# schematic.net
KiCad netlist of a schematic drawn in Altium Designer
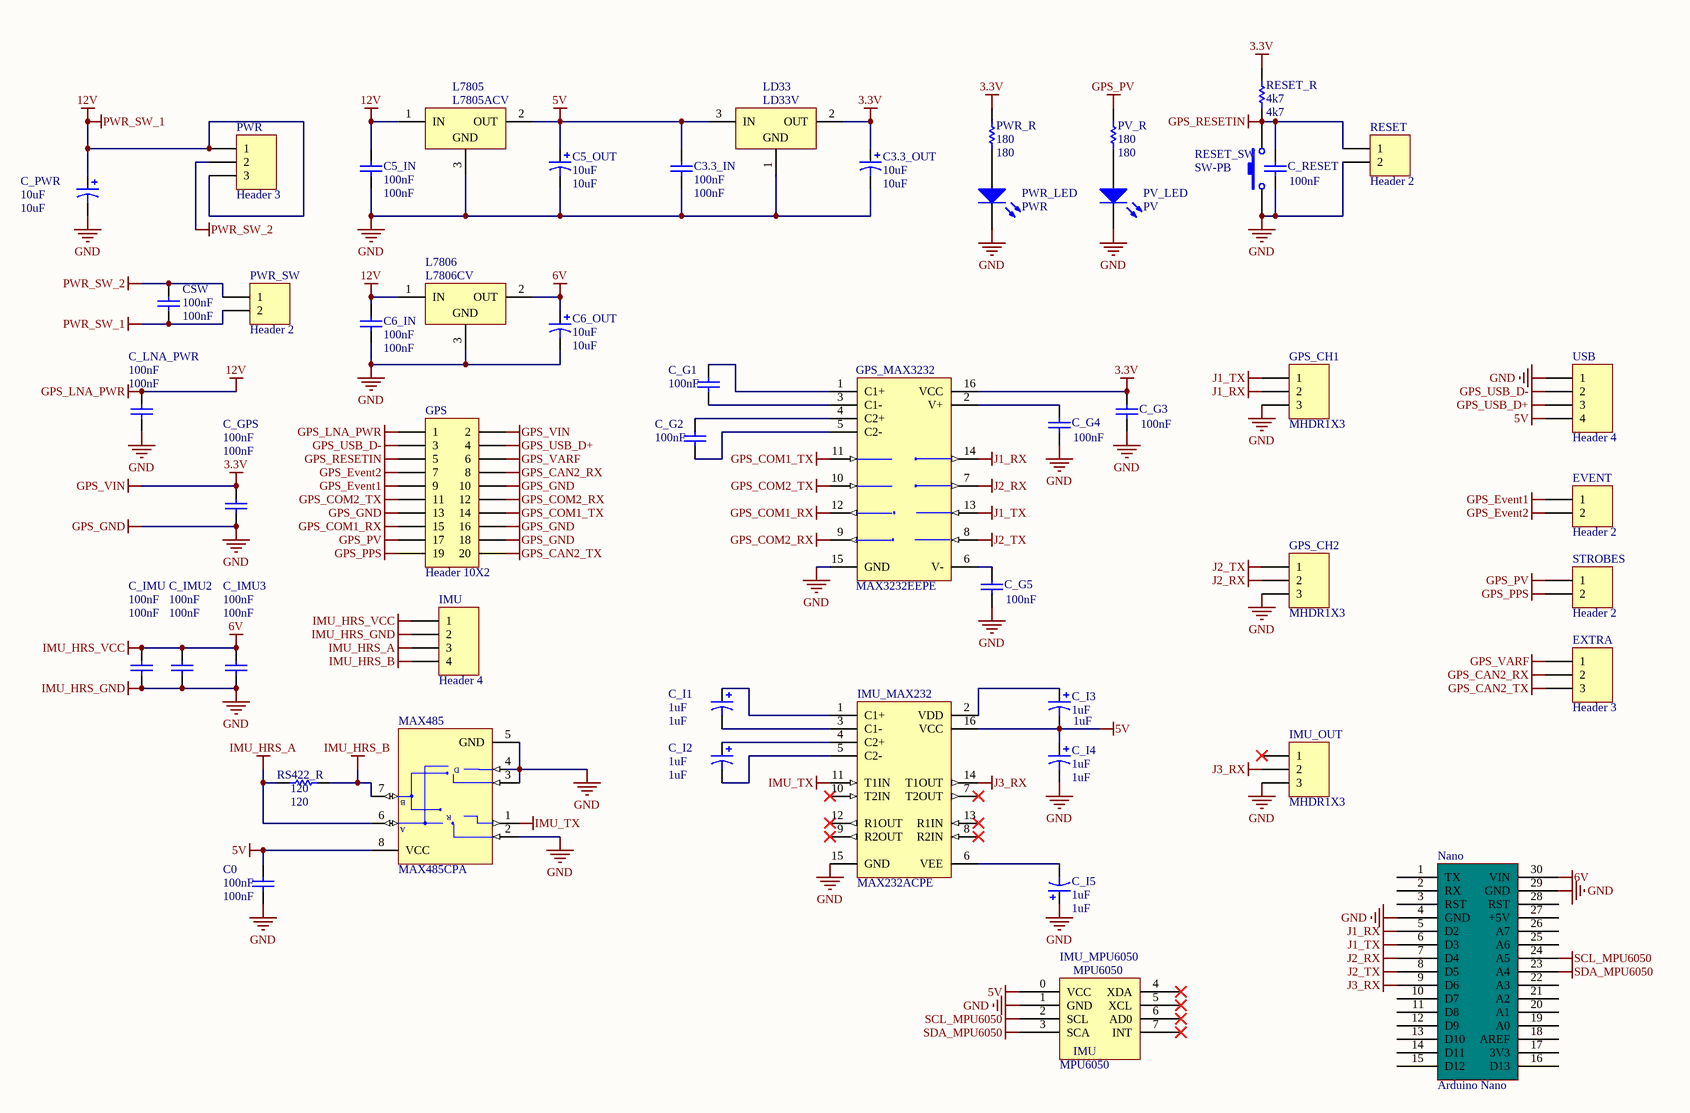
[diagram p0: schematic.SchDoc]

(export (version "E")
  (design (tool "Eeschema 10.0.6"))
  (components
    (comp (ref "C0")
      (value "100nF")
      (footprint "C_NANO_HOLES")
      (description "Capacitor")
      (fields (field (name "ALTIUM_VALUE") "100nF") (field (name "PUBLISHER") "Altium Limited"))
      (libsource (lib "Miscellaneous Devices") (part "Cap"))
    )
    (comp (ref "C3.3_IN")
      (value "100nF")
      (footprint "C_NANO_HOLES")
      (description "Capacitor")
      (fields (field (name "ALTIUM_VALUE") "100nF") (field (name "PUBLISHER") "Altium Limited"))
      (libsource (lib "Miscellaneous Devices") (part "Cap"))
    )
    (comp (ref "C3.3_OUT")
      (value "10uF")
      (footprint "B")
      (description "Polarized Capacitor (Radial)")
      (fields (field (name "ALTIUM_VALUE") "10uF") (field (name "PUBLISHER") "Altium Limited"))
      (libsource (lib "Miscellaneous Devices") (part "Cap Pol1"))
    )
    (comp (ref "C5_IN")
      (value "100nF")
      (footprint "C_NANO_HOLES")
      (description "Capacitor")
      (fields (field (name "ALTIUM_VALUE") "100nF") (field (name "PUBLISHER") "Altium Limited"))
      (libsource (lib "Miscellaneous Devices") (part "Cap"))
    )
    (comp (ref "C5_OUT")
      (value "10uF")
      (footprint "B")
      (description "Polarized Capacitor (Radial)")
      (fields (field (name "ALTIUM_VALUE") "10uF") (field (name "PUBLISHER") "Altium Limited"))
      (libsource (lib "Miscellaneous Devices") (part "Cap Pol1"))
    )
    (comp (ref "C6_IN")
      (value "100nF")
      (footprint "C_NANO_HOLES")
      (description "Capacitor")
      (fields (field (name "ALTIUM_VALUE") "100nF") (field (name "PUBLISHER") "Altium Limited"))
      (libsource (lib "Miscellaneous Devices") (part "Cap"))
    )
    (comp (ref "C6_OUT")
      (value "10uF")
      (footprint "B")
      (description "Polarized Capacitor (Radial)")
      (fields (field (name "ALTIUM_VALUE") "10uF") (field (name "PUBLISHER") "Altium Limited"))
      (libsource (lib "Miscellaneous Devices") (part "Cap Pol1"))
    )
    (comp (ref "CSW")
      (value "100nF")
      (footprint "C_NANO_HOLES")
      (description "Capacitor")
      (fields (field (name "ALTIUM_VALUE") "100nF") (field (name "PUBLISHER") "Altium Limited"))
      (libsource (lib "Miscellaneous Devices") (part "Cap"))
    )
    (comp (ref "C_G1")
      (value "100nF")
      (footprint "C_NANO_HOLES")
      (description "Capacitor")
      (fields (field (name "PUBLISHER") "Altium Limited"))
      (libsource (lib "Miscellaneous Devices") (part "Cap"))
    )
    (comp (ref "C_G2")
      (value "100nF")
      (footprint "C_NANO_HOLES")
      (description "Capacitor")
      (fields (field (name "PUBLISHER") "Altium Limited"))
      (libsource (lib "Miscellaneous Devices") (part "Cap"))
    )
    (comp (ref "C_G3")
      (value "100nF")
      (footprint "C_NANO_HOLES")
      (description "Capacitor")
      (fields (field (name "PUBLISHER") "Altium Limited"))
      (libsource (lib "Miscellaneous Devices") (part "Cap"))
    )
    (comp (ref "C_G4")
      (value "100nF")
      (footprint "C_NANO_HOLES")
      (description "Capacitor")
      (fields (field (name "PUBLISHER") "Altium Limited"))
      (libsource (lib "Miscellaneous Devices") (part "Cap"))
    )
    (comp (ref "C_G5")
      (value "100nF")
      (footprint "C_NANO_HOLES")
      (description "Capacitor")
      (fields (field (name "PUBLISHER") "Altium Limited"))
      (libsource (lib "Miscellaneous Devices") (part "Cap"))
    )
    (comp (ref "C_GPS")
      (value "100nF")
      (footprint "C_NANO_HOLES")
      (description "Capacitor")
      (fields (field (name "ALTIUM_VALUE") "100nF") (field (name "PUBLISHER") "Altium Limited"))
      (libsource (lib "Miscellaneous Devices") (part "Cap"))
    )
    (comp (ref "C_I1")
      (value "1uF")
      (footprint "B")
      (description "Polarized Capacitor (Radial)")
      (fields (field (name "ALTIUM_VALUE") "1uF") (field (name "PUBLISHER") "Altium Limited"))
      (libsource (lib "Miscellaneous Devices") (part "Cap Pol1"))
    )
    (comp (ref "C_I2")
      (value "1uF")
      (footprint "B")
      (description "Polarized Capacitor (Radial)")
      (fields (field (name "ALTIUM_VALUE") "1uF") (field (name "PUBLISHER") "Altium Limited"))
      (libsource (lib "Miscellaneous Devices") (part "Cap Pol1"))
    )
    (comp (ref "C_I3")
      (value "1uF")
      (footprint "B")
      (description "Polarized Capacitor (Radial)")
      (fields (field (name "ALTIUM_VALUE") "1uF") (field (name "PUBLISHER") "Altium Limited"))
      (libsource (lib "Miscellaneous Devices") (part "Cap Pol1"))
    )
    (comp (ref "C_I4")
      (value "1uF")
      (footprint "B")
      (description "Polarized Capacitor (Radial)")
      (fields (field (name "ALTIUM_VALUE") "1uF") (field (name "PUBLISHER") "Altium Limited"))
      (libsource (lib "Miscellaneous Devices") (part "Cap Pol1"))
    )
    (comp (ref "C_I5")
      (value "1uF")
      (footprint "B")
      (description "Polarized Capacitor (Radial)")
      (fields (field (name "ALTIUM_VALUE") "1uF") (field (name "PUBLISHER") "Altium Limited"))
      (libsource (lib "Miscellaneous Devices") (part "Cap Pol1"))
    )
    (comp (ref "C_IMU")
      (value "100nF")
      (footprint "C_NANO_HOLES")
      (description "Capacitor")
      (fields (field (name "ALTIUM_VALUE") "100nF") (field (name "PUBLISHER") "Altium Limited"))
      (libsource (lib "Miscellaneous Devices") (part "Cap"))
    )
    (comp (ref "C_IMU2")
      (value "100nF")
      (footprint "C_NANO_HOLES")
      (description "Capacitor")
      (fields (field (name "ALTIUM_VALUE") "100nF") (field (name "PUBLISHER") "Altium Limited"))
      (libsource (lib "Miscellaneous Devices") (part "Cap"))
    )
    (comp (ref "C_IMU3")
      (value "100nF")
      (footprint "C_NANO_HOLES")
      (description "Capacitor")
      (fields (field (name "ALTIUM_VALUE") "100nF") (field (name "PUBLISHER") "Altium Limited"))
      (libsource (lib "Miscellaneous Devices") (part "Cap"))
    )
    (comp (ref "C_LNA_PWR")
      (value "100nF")
      (footprint "C_NANO_HOLES")
      (description "Capacitor")
      (fields (field (name "ALTIUM_VALUE") "100nF") (field (name "PUBLISHER") "Altium Limited"))
      (libsource (lib "Miscellaneous Devices") (part "Cap"))
    )
    (comp (ref "C_PWR")
      (value "10uF")
      (footprint "B")
      (description "Polarized Capacitor (Radial)")
      (fields (field (name "ALTIUM_VALUE") "10uF") (field (name "PUBLISHER") "Altium Limited"))
      (libsource (lib "Miscellaneous Devices") (part "Cap Pol1"))
    )
    (comp (ref "C_RESET")
      (value "100nF")
      (footprint "C_NANO_HOLES")
      (description "Capacitor")
      (fields (field (name "PUBLISHER") "Altium Limited"))
      (libsource (lib "Miscellaneous Devices") (part "Cap"))
    )
    (comp (ref "EVENT")
      (value "Header 2")
      (footprint "HDR1X2")
      (description "Header, 2-Pin")
      (fields (field (name "PUBLISHER") "Altium Limited"))
      (libsource (lib "Miscellaneous Connectors") (part "Header 2"))
    )
    (comp (ref "EXTRA")
      (value "Header 3")
      (footprint "HDR1X3")
      (description "Header, 3-Pin")
      (fields (field (name "PUBLISHER") "Altium Limited"))
      (libsource (lib "Miscellaneous Connectors") (part "Header 3"))
    )
    (comp (ref "GPS")
      (value "Header 10X2")
      (footprint "HDR2x10_2mm")
      (description "Header, 10-Pin, Dual row")
      (fields (field (name "PUBLISHER") "Altium Limited"))
      (libsource (lib "Miscellaneous Connectors") (part "Header 10X2"))
    )
    (comp (ref "GPS_CH1")
      (value "MHDR1X3")
      (footprint "HDR1X3")
      (description "Header, 3-Pin")
      (fields (field (name "PUBLISHER") "Altium Limited"))
      (libsource (lib "Miscellaneous Connectors") (part "MHDR1X3"))
    )
    (comp (ref "GPS_CH2")
      (value "MHDR1X3")
      (footprint "HDR1X3")
      (description "Header, 3-Pin")
      (fields (field (name "PUBLISHER") "Altium Limited"))
      (libsource (lib "Miscellaneous Connectors") (part "MHDR1X3"))
    )
    (comp (ref "GPS_MAX3232")
      (value "MAX3232EEPE")
      (footprint "Maxim Footprints:PE16")
      (description "±15kV ESD-Protected, 3.0V to 5.5V, Low-Power, up to 250kbps, True RS-232 Transceiver")
      (fields (field (name "PUBLISHER") "Altium Limited"))
      (libsource (lib "Maxim Communication Transceiver") (part "MAX3232EEPE"))
    )
    (comp (ref "IMU")
      (value "Header 4")
      (footprint "HDR1X4")
      (description "Header, 4-Pin")
      (fields (field (name "PUBLISHER") "Altium Limited"))
      (libsource (lib "Miscellaneous Connectors") (part "Header 4"))
    )
    (comp (ref "IMU_MAX232")
      (value "MAX232ACPE")
      (footprint "PE16A")
      (description "+5V Powered, Multi-Channel RS-232 Driver/Receiver")
      (fields (field (name "PUBLISHER") "Altium Limited"))
      (libsource (lib "Maxim Communication Transceiver") (part "MAX232ACPE"))
    )
    (comp (ref "IMU_MPU6050")
      (value "MPU6050")
      (footprint "MPU6050")
      (libsource (lib "IMU_MPU6050") (part "Component_1"))
    )
    (comp (ref "IMU_OUT")
      (value "MHDR1X3")
      (footprint "HDR1X3")
      (description "Header, 3-Pin")
      (fields (field (name "PUBLISHER") "Altium Limited"))
      (libsource (lib "Miscellaneous Connectors") (part "MHDR1X3"))
    )
    (comp (ref "L7805")
      (value "L7805ACV")
      (footprint "TO220ABN")
      (description "Precision 1A Regulator")
      (fields (field (name "PUBLISHER") "Altium Limited"))
      (libsource (lib "ST Power Mgt Voltage Regulator") (part "L7805ACV"))
    )
    (comp (ref "L7806")
      (value "L7806CV")
      (footprint "TO220ABN")
      (description "Positive Voltage Regulator")
      (fields (field (name "PUBLISHER") "Altium Limited"))
      (libsource (lib "ST Power Mgt Voltage Regulator") (part "L7806CV"))
    )
    (comp (ref "LD33")
      (value "LD33V")
      (footprint "T03B")
      (description "800mA Low-Dropout Linear Regulator")
      (fields
        (field (name "PARTNUMBER") "LM1117T-3.3")
        (field (name "MANUFACTURER") "National Semiconductor")
        (field (name "PUBLISHER") "Altium Limited")
      )
      (libsource (lib "NSC LDO") (part "LM1117T-3.3"))
    )
    (comp (ref "MAX485")
      (value "MAX485CPA")
      (footprint "PA8")
      (description "Low-Power, Slew-Rate-Limited RS-485/RS-422 Transceiver")
      (fields (field (name "PUBLISHER") "Altium Limited"))
      (libsource (lib "Maxim Communication Transceiver") (part "MAX485CPA"))
    )
    (comp (ref "Nano")
      (value "Arduino Nano")
      (footprint "Nano:ArduinoNano")
      (libsource (lib "Nano") (part "Component_1"))
    )
    (comp (ref "PV_LED")
      (value "PV")
      (footprint "HDR1X2")
      (description "Typical INFRARED GaAs LED")
      (fields (field (name "PUBLISHER") "Altium Limited"))
      (libsource (lib "Miscellaneous Devices") (part "LED0"))
    )
    (comp (ref "PV_R")
      (value "180")
      (footprint "AXIAL-0.3")
      (description "Resistor")
      (fields (field (name "ALTIUM_VALUE") "180") (field (name "PUBLISHER") "Altium Limited"))
      (libsource (lib "Miscellaneous Devices") (part "Res1"))
    )
    (comp (ref "PWR")
      (value "Header 3")
      (footprint "Miscellaneous Connectors:HDR1X3")
      (description "Header, 3-Pin, Right Angle")
      (fields (field (name "PUBLISHER") "Altium Limited"))
      (libsource (lib "Miscellaneous Connectors") (part "Header 3H"))
    )
    (comp (ref "PWR_LED")
      (value "PWR")
      (footprint "HDR1X2")
      (description "Typical INFRARED GaAs LED")
      (fields (field (name "PUBLISHER") "Altium Limited"))
      (libsource (lib "Miscellaneous Devices") (part "LED0"))
    )
    (comp (ref "PWR_R")
      (value "180")
      (footprint "AXIAL-0.3")
      (description "Resistor")
      (fields (field (name "ALTIUM_VALUE") "180") (field (name "PUBLISHER") "Altium Limited"))
      (libsource (lib "Miscellaneous Devices") (part "Res1"))
    )
    (comp (ref "PWR_SW")
      (value "Header 2")
      (footprint "Miscellaneous Connectors:HDR1X2")
      (description "Header, 2-Pin, Right Angle")
      (fields (field (name "PUBLISHER") "Altium Limited"))
      (libsource (lib "Miscellaneous Connectors") (part "Header 2H"))
    )
    (comp (ref "RESET")
      (value "Header 2")
      (footprint "Miscellaneous Connectors:HDR1X2")
      (description "Header, 2-Pin, Right Angle")
      (fields (field (name "PUBLISHER") "Altium Limited"))
      (libsource (lib "Miscellaneous Connectors") (part "Header 2H"))
    )
    (comp (ref "RESET_R")
      (value "4k7")
      (footprint "AXIAL-0.3")
      (description "Resistor")
      (fields (field (name "ALTIUM_VALUE") "4k7") (field (name "PUBLISHER") "Altium Limited"))
      (libsource (lib "Miscellaneous Devices") (part "Res1"))
    )
    (comp (ref "RESET_SW")
      (value "SW-PB")
      (footprint "PUSHBUTTON")
      (description "Switch")
      (fields (field (name "PUBLISHER") "Altium Limited"))
      (libsource (lib "Miscellaneous Devices") (part "SW-PB"))
    )
    (comp (ref "RS422_R")
      (value "120")
      (footprint "AXIAL-0.3")
      (description "Resistor")
      (fields (field (name "ALTIUM_VALUE") "120") (field (name "PUBLISHER") "Altium Limited"))
      (libsource (lib "Miscellaneous Devices") (part "Res1"))
    )
    (comp (ref "STROBES")
      (value "Header 2")
      (footprint "HDR1X2")
      (description "Header, 2-Pin")
      (fields (field (name "PUBLISHER") "Altium Limited"))
      (libsource (lib "Miscellaneous Connectors") (part "Header 2"))
    )
    (comp (ref "USB")
      (value "Header 4")
      (footprint "HDR1X4")
      (description "Header, 4-Pin")
      (fields (field (name "PUBLISHER") "Altium Limited"))
      (libsource (lib "Miscellaneous Connectors") (part "Header 4"))
    )
  )
  (nets
    (net (code "1") (name "3.3V") (class "Default")
      (node (ref "C3.3_OUT") (pin "1") (pinfunction "1_1") (pintype "passive"))
      (node (ref "C_G3") (pin "2") (pinfunction "2_2") (pintype "passive"))
      (node (ref "C_GPS") (pin "2") (pinfunction "2_2") (pintype "passive"))
      (node (ref "GPS") (pin "2") (pinfunction "2_2") (pintype "passive"))
      (node (ref "GPS_MAX3232") (pin "16") (pinfunction "VCC_16") (pintype "power_in"))
      (node (ref "LD33") (pin "2") (pinfunction "OUT_2") (pintype "power_in"))
      (node (ref "PWR_R") (pin "2") (pinfunction "2_2") (pintype "passive"))
      (node (ref "RESET_R") (pin "2") (pinfunction "2_2") (pintype "passive"))
    )
    (net (code "2") (name "5V") (class "Default")
      (node (ref "C0") (pin "2") (pinfunction "2_2") (pintype "passive"))
      (node (ref "C3.3_IN") (pin "1") (pinfunction "1_1") (pintype "passive"))
      (node (ref "C5_OUT") (pin "1") (pinfunction "1_1") (pintype "passive"))
      (node (ref "C_I3") (pin "2") (pinfunction "2_2") (pintype "passive"))
      (node (ref "C_I4") (pin "1") (pinfunction "1_1") (pintype "passive"))
      (node (ref "IMU_MAX232") (pin "16") (pinfunction "VCC_16") (pintype "power_in"))
      (node (ref "IMU_MPU6050") (pin "0") (pinfunction "VCC_0") (pintype "passive"))
      (node (ref "L7805") (pin "2") (pinfunction "OUT_2") (pintype "power_in"))
      (node (ref "LD33") (pin "3") (pinfunction "IN_3") (pintype "power_in"))
      (node (ref "MAX485") (pin "8") (pinfunction "VCC_8") (pintype "power_in"))
      (node (ref "USB") (pin "4") (pinfunction "4_4") (pintype "passive"))
    )
    (net (code "3") (name "6V") (class "Default")
      (node (ref "C6_OUT") (pin "1") (pinfunction "1_1") (pintype "passive"))
      (node (ref "C_IMU") (pin "2") (pinfunction "2_2") (pintype "passive"))
      (node (ref "C_IMU2") (pin "2") (pinfunction "2_2") (pintype "passive"))
      (node (ref "C_IMU3") (pin "2") (pinfunction "2_2") (pintype "passive"))
      (node (ref "IMU") (pin "1") (pinfunction "1_1") (pintype "passive"))
      (node (ref "L7806") (pin "2") (pinfunction "OUT_2") (pintype "power_in"))
      (node (ref "Nano") (pin "30") (pinfunction "VIN_30") (pintype "passive"))
    )
    (net (code "4") (name "12V") (class "Default")
      (node (ref "C5_IN") (pin "1") (pinfunction "1_1") (pintype "passive"))
      (node (ref "C6_IN") (pin "1") (pinfunction "1_1") (pintype "passive"))
      (node (ref "CSW") (pin "2") (pinfunction "2_2") (pintype "passive"))
      (node (ref "C_LNA_PWR") (pin "2") (pinfunction "2_2") (pintype "passive"))
      (node (ref "C_PWR") (pin "1") (pinfunction "1_1") (pintype "passive"))
      (node (ref "GPS") (pin "1") (pinfunction "1_1") (pintype "passive"))
      (node (ref "L7805") (pin "1") (pinfunction "IN_1") (pintype "power_in"))
      (node (ref "L7806") (pin "1") (pinfunction "IN_1") (pintype "power_in"))
      (node (ref "PWR") (pin "1") (pinfunction "1_1") (pintype "passive"))
      (node (ref "PWR") (pin "3") (pinfunction "3_3") (pintype "passive"))
      (node (ref "PWR_SW") (pin "2") (pinfunction "2_2") (pintype "passive"))
    )
    (net (code "5") (name "GND") (class "Default")
      (node (ref "C0") (pin "1") (pinfunction "1_1") (pintype "passive"))
      (node (ref "C3.3_IN") (pin "2") (pinfunction "2_2") (pintype "passive"))
      (node (ref "C3.3_OUT") (pin "2") (pinfunction "2_2") (pintype "passive"))
      (node (ref "C5_IN") (pin "2") (pinfunction "2_2") (pintype "passive"))
      (node (ref "C5_OUT") (pin "2") (pinfunction "2_2") (pintype "passive"))
      (node (ref "C6_IN") (pin "2") (pinfunction "2_2") (pintype "passive"))
      (node (ref "C6_OUT") (pin "2") (pinfunction "2_2") (pintype "passive"))
      (node (ref "C_G3") (pin "1") (pinfunction "1_1") (pintype "passive"))
      (node (ref "C_G4") (pin "1") (pinfunction "1_1") (pintype "passive"))
      (node (ref "C_G5") (pin "1") (pinfunction "1_1") (pintype "passive"))
      (node (ref "C_GPS") (pin "1") (pinfunction "1_1") (pintype "passive"))
      (node (ref "C_I4") (pin "2") (pinfunction "2_2") (pintype "passive"))
      (node (ref "C_I5") (pin "1") (pinfunction "1_1") (pintype "passive"))
      (node (ref "C_IMU") (pin "1") (pinfunction "1_1") (pintype "passive"))
      (node (ref "C_IMU2") (pin "1") (pinfunction "1_1") (pintype "passive"))
      (node (ref "C_IMU3") (pin "1") (pinfunction "1_1") (pintype "passive"))
      (node (ref "C_LNA_PWR") (pin "1") (pinfunction "1_1") (pintype "passive"))
      (node (ref "C_PWR") (pin "2") (pinfunction "2_2") (pintype "passive"))
      (node (ref "C_RESET") (pin "1") (pinfunction "1_1") (pintype "passive"))
      (node (ref "GPS") (pin "10") (pinfunction "10_10") (pintype "passive"))
      (node (ref "GPS") (pin "13") (pinfunction "13_13") (pintype "passive"))
      (node (ref "GPS") (pin "16") (pinfunction "16_16") (pintype "passive"))
      (node (ref "GPS") (pin "18") (pinfunction "18_18") (pintype "passive"))
      (node (ref "GPS_CH1") (pin "3") (pinfunction "3_3") (pintype "passive"))
      (node (ref "GPS_CH2") (pin "3") (pinfunction "3_3") (pintype "passive"))
      (node (ref "GPS_MAX3232") (pin "15") (pinfunction "GND_15") (pintype "power_in"))
      (node (ref "IMU") (pin "2") (pinfunction "2_2") (pintype "passive"))
      (node (ref "IMU_MAX232") (pin "15") (pinfunction "GND_15") (pintype "power_in"))
      (node (ref "IMU_MPU6050") (pin "1") (pinfunction "GND_1") (pintype "passive"))
      (node (ref "IMU_OUT") (pin "3") (pinfunction "3_3") (pintype "passive"))
      (node (ref "L7805") (pin "3") (pinfunction "GND_3") (pintype "power_in"))
      (node (ref "L7806") (pin "3") (pinfunction "GND_3") (pintype "power_in"))
      (node (ref "LD33") (pin "1") (pinfunction "GND_1") (pintype "power_in"))
      (node (ref "MAX485") (pin "2") (pinfunction "~{RE}_2") (pintype "input"))
      (node (ref "MAX485") (pin "3") (pinfunction "DE_3") (pintype "input"))
      (node (ref "MAX485") (pin "4") (pinfunction "DI_4") (pintype "input"))
      (node (ref "MAX485") (pin "5") (pinfunction "GND_5") (pintype "power_in"))
      (node (ref "Nano") (pin "29") (pinfunction "GND_29") (pintype "passive"))
      (node (ref "Nano") (pin "4") (pinfunction "GND_4") (pintype "passive"))
      (node (ref "PV_LED") (pin "2") (pinfunction "K_2") (pintype "passive"))
      (node (ref "PWR_LED") (pin "2") (pinfunction "K_2") (pintype "passive"))
      (node (ref "RESET") (pin "2") (pinfunction "2_2") (pintype "passive"))
      (node (ref "RESET_SW") (pin "1") (pinfunction "1_1") (pintype "passive"))
      (node (ref "USB") (pin "1") (pinfunction "1_1") (pintype "passive"))
    )
    (net (code "6") (name "GPS_CAN2_RX") (class "Default")
      (node (ref "EXTRA") (pin "2") (pinfunction "2_2") (pintype "passive"))
      (node (ref "GPS") (pin "8") (pinfunction "8_8") (pintype "passive"))
    )
    (net (code "7") (name "GPS_CAN2_TX") (class "Default")
      (node (ref "EXTRA") (pin "3") (pinfunction "3_3") (pintype "passive"))
      (node (ref "GPS") (pin "20") (pinfunction "20_20") (pintype "passive"))
    )
    (net (code "8") (name "GPS_COM1_RX") (class "Default")
      (node (ref "GPS") (pin "15") (pinfunction "15_15") (pintype "passive"))
      (node (ref "GPS_MAX3232") (pin "12") (pinfunction "R1OUT_12") (pintype "output"))
    )
    (net (code "9") (name "GPS_COM1_TX") (class "Default")
      (node (ref "GPS") (pin "14") (pinfunction "14_14") (pintype "passive"))
      (node (ref "GPS_MAX3232") (pin "11") (pinfunction "T1IN_11") (pintype "input"))
    )
    (net (code "10") (name "GPS_COM2_RX") (class "Default")
      (node (ref "GPS") (pin "12") (pinfunction "12_12") (pintype "passive"))
      (node (ref "GPS_MAX3232") (pin "9") (pinfunction "R2OUT_9") (pintype "output"))
    )
    (net (code "11") (name "GPS_COM2_TX") (class "Default")
      (node (ref "GPS") (pin "11") (pinfunction "11_11") (pintype "passive"))
      (node (ref "GPS_MAX3232") (pin "10") (pinfunction "T2IN_10") (pintype "input"))
    )
    (net (code "12") (name "GPS_Event1") (class "Default")
      (node (ref "EVENT") (pin "1") (pinfunction "1_1") (pintype "passive"))
      (node (ref "GPS") (pin "9") (pinfunction "9_9") (pintype "passive"))
    )
    (net (code "13") (name "GPS_Event2") (class "Default")
      (node (ref "EVENT") (pin "2") (pinfunction "2_2") (pintype "passive"))
      (node (ref "GPS") (pin "7") (pinfunction "7_7") (pintype "passive"))
    )
    (net (code "14") (name "GPS_PPS") (class "Default")
      (node (ref "GPS") (pin "19") (pinfunction "19_19") (pintype "passive"))
      (node (ref "STROBES") (pin "2") (pinfunction "2_2") (pintype "passive"))
    )
    (net (code "15") (name "GPS_PV") (class "Default")
      (node (ref "GPS") (pin "17") (pinfunction "17_17") (pintype "passive"))
      (node (ref "PV_R") (pin "2") (pinfunction "2_2") (pintype "passive"))
      (node (ref "STROBES") (pin "1") (pinfunction "1_1") (pintype "passive"))
    )
    (net (code "16") (name "GPS_RESETIN") (class "Default")
      (node (ref "C_RESET") (pin "2") (pinfunction "2_2") (pintype "passive"))
      (node (ref "GPS") (pin "5") (pinfunction "5_5") (pintype "passive"))
      (node (ref "RESET") (pin "1") (pinfunction "1_1") (pintype "passive"))
      (node (ref "RESET_R") (pin "1") (pinfunction "1_1") (pintype "passive"))
      (node (ref "RESET_SW") (pin "2") (pinfunction "2_2") (pintype "passive"))
    )
    (net (code "17") (name "GPS_USB_D+") (class "Default")
      (node (ref "GPS") (pin "4") (pinfunction "4_4") (pintype "passive"))
      (node (ref "USB") (pin "3") (pinfunction "3_3") (pintype "passive"))
    )
    (net (code "18") (name "GPS_USB_D-") (class "Default")
      (node (ref "GPS") (pin "3") (pinfunction "3_3") (pintype "passive"))
      (node (ref "USB") (pin "2") (pinfunction "2_2") (pintype "passive"))
    )
    (net (code "19") (name "GPS_VARF") (class "Default")
      (node (ref "EXTRA") (pin "1") (pinfunction "1_1") (pintype "passive"))
      (node (ref "GPS") (pin "6") (pinfunction "6_6") (pintype "passive"))
    )
    (net (code "20") (name "IMU_HRS_A") (class "Default")
      (node (ref "IMU") (pin "3") (pinfunction "3_3") (pintype "passive"))
      (node (ref "MAX485") (pin "6") (pinfunction "A_6") (pintype "bidirectional"))
      (node (ref "RS422_R") (pin "1") (pinfunction "1_1") (pintype "passive"))
    )
    (net (code "21") (name "IMU_HRS_B") (class "Default")
      (node (ref "IMU") (pin "4") (pinfunction "4_4") (pintype "passive"))
      (node (ref "MAX485") (pin "7") (pinfunction "B_7") (pintype "bidirectional"))
      (node (ref "RS422_R") (pin "2") (pinfunction "2_2") (pintype "passive"))
    )
    (net (code "22") (name "IMU_TX") (class "Default")
      (node (ref "IMU_MAX232") (pin "11") (pinfunction "T1IN_11") (pintype "input"))
      (node (ref "MAX485") (pin "1") (pinfunction "RO_1") (pintype "output"))
    )
    (net (code "23") (name "J1_RX") (class "Default")
      (node (ref "GPS_CH1") (pin "2") (pinfunction "2_2") (pintype "passive"))
      (node (ref "GPS_MAX3232") (pin "14") (pinfunction "T1OUT_14") (pintype "output"))
      (node (ref "Nano") (pin "5") (pinfunction "D2_5") (pintype "passive"))
    )
    (net (code "24") (name "J1_TX") (class "Default")
      (node (ref "GPS_CH1") (pin "1") (pinfunction "1_1") (pintype "passive"))
      (node (ref "GPS_MAX3232") (pin "13") (pinfunction "R1IN_13") (pintype "input"))
      (node (ref "Nano") (pin "6") (pinfunction "D3_6") (pintype "passive"))
    )
    (net (code "25") (name "J2_RX") (class "Default")
      (node (ref "GPS_CH2") (pin "2") (pinfunction "2_2") (pintype "passive"))
      (node (ref "GPS_MAX3232") (pin "7") (pinfunction "T2OUT_7") (pintype "output"))
      (node (ref "Nano") (pin "7") (pinfunction "D4_7") (pintype "passive"))
    )
    (net (code "26") (name "J2_TX") (class "Default")
      (node (ref "GPS_CH2") (pin "1") (pinfunction "1_1") (pintype "passive"))
      (node (ref "GPS_MAX3232") (pin "8") (pinfunction "R2IN_8") (pintype "input"))
      (node (ref "Nano") (pin "8") (pinfunction "D5_8") (pintype "passive"))
    )
    (net (code "27") (name "J3_RX") (class "Default")
      (node (ref "IMU_MAX232") (pin "14") (pinfunction "T1OUT_14") (pintype "output"))
      (node (ref "IMU_OUT") (pin "2") (pinfunction "2_2") (pintype "passive"))
      (node (ref "Nano") (pin "9") (pinfunction "D6_9") (pintype "passive"))
    )
    (net (code "28") (name "Net-(GPS_MAX3232-C1+)") (class "Default")
      (node (ref "C_G1") (pin "2") (pinfunction "2_2") (pintype "passive"))
      (node (ref "GPS_MAX3232") (pin "1") (pinfunction "C1+_1") (pintype "passive"))
    )
    (net (code "29") (name "Net-(GPS_MAX3232-C1-)") (class "Default")
      (node (ref "C_G1") (pin "1") (pinfunction "1_1") (pintype "passive"))
      (node (ref "GPS_MAX3232") (pin "3") (pinfunction "C1-_3") (pintype "passive"))
    )
    (net (code "30") (name "Net-(GPS_MAX3232-C2+)") (class "Default")
      (node (ref "C_G2") (pin "2") (pinfunction "2_2") (pintype "passive"))
      (node (ref "GPS_MAX3232") (pin "4") (pinfunction "C2+_4") (pintype "passive"))
    )
    (net (code "31") (name "Net-(GPS_MAX3232-C2-)") (class "Default")
      (node (ref "C_G2") (pin "1") (pinfunction "1_1") (pintype "passive"))
      (node (ref "GPS_MAX3232") (pin "5") (pinfunction "C2-_5") (pintype "passive"))
    )
    (net (code "32") (name "Net-(GPS_MAX3232-V+)") (class "Default")
      (node (ref "C_G4") (pin "2") (pinfunction "2_2") (pintype "passive"))
      (node (ref "GPS_MAX3232") (pin "2") (pinfunction "V+_2") (pintype "power_in"))
    )
    (net (code "33") (name "Net-(GPS_MAX3232-V-)") (class "Default")
      (node (ref "C_G5") (pin "2") (pinfunction "2_2") (pintype "passive"))
      (node (ref "GPS_MAX3232") (pin "6") (pinfunction "V-_6") (pintype "power_in"))
    )
    (net (code "34") (name "Net-(IMU_MAX232-C1+)") (class "Default")
      (node (ref "C_I1") (pin "1") (pinfunction "1_1") (pintype "passive"))
      (node (ref "IMU_MAX232") (pin "1") (pinfunction "C1+_1") (pintype "passive"))
    )
    (net (code "35") (name "Net-(IMU_MAX232-C1-)") (class "Default")
      (node (ref "C_I1") (pin "2") (pinfunction "2_2") (pintype "passive"))
      (node (ref "IMU_MAX232") (pin "3") (pinfunction "C1-_3") (pintype "passive"))
    )
    (net (code "36") (name "Net-(IMU_MAX232-C2+)") (class "Default")
      (node (ref "C_I2") (pin "1") (pinfunction "1_1") (pintype "passive"))
      (node (ref "IMU_MAX232") (pin "4") (pinfunction "C2+_4") (pintype "passive"))
    )
    (net (code "37") (name "Net-(IMU_MAX232-C2-)") (class "Default")
      (node (ref "C_I2") (pin "2") (pinfunction "2_2") (pintype "passive"))
      (node (ref "IMU_MAX232") (pin "5") (pinfunction "C2-_5") (pintype "passive"))
    )
    (net (code "38") (name "Net-(IMU_MAX232-VDD)") (class "Default")
      (node (ref "C_I3") (pin "1") (pinfunction "1_1") (pintype "passive"))
      (node (ref "IMU_MAX232") (pin "2") (pinfunction "VDD_2") (pintype "power_in"))
    )
    (net (code "39") (name "Net-(IMU_MAX232-VEE)") (class "Default")
      (node (ref "C_I5") (pin "2") (pinfunction "2_2") (pintype "passive"))
      (node (ref "IMU_MAX232") (pin "6") (pinfunction "VEE_6") (pintype "power_in"))
    )
    (net (code "40") (name "Net-(PV_LED-A)") (class "Default")
      (node (ref "PV_LED") (pin "1") (pinfunction "A_1") (pintype "passive"))
      (node (ref "PV_R") (pin "1") (pinfunction "1_1") (pintype "passive"))
    )
    (net (code "41") (name "Net-(PWR_LED-A)") (class "Default")
      (node (ref "PWR_LED") (pin "1") (pinfunction "A_1") (pintype "passive"))
      (node (ref "PWR_R") (pin "1") (pinfunction "1_1") (pintype "passive"))
    )
    (net (code "42") (name "PWR_SW_2") (class "Default")
      (node (ref "CSW") (pin "1") (pinfunction "1_1") (pintype "passive"))
      (node (ref "PWR") (pin "2") (pinfunction "2_2") (pintype "passive"))
      (node (ref "PWR_SW") (pin "1") (pinfunction "1_1") (pintype "passive"))
    )
    (net (code "43") (name "SCL_MPU6050") (class "Default")
      (node (ref "IMU_MPU6050") (pin "2") (pinfunction "SCL_2") (pintype "passive"))
      (node (ref "Nano") (pin "24") (pinfunction "A5_24") (pintype "passive"))
    )
    (net (code "44") (name "SDA_MPU6050") (class "Default")
      (node (ref "IMU_MPU6050") (pin "3") (pinfunction "SCA_3") (pintype "passive"))
      (node (ref "Nano") (pin "23") (pinfunction "A4_23") (pintype "passive"))
    )
    (net (code "45") (name "unconnected-(IMU_MAX232-R1IN-Pad13)") (class "Default")
      (node (ref "IMU_MAX232") (pin "13") (pinfunction "R1IN_13") (pintype "input+no_connect"))
    )
    (net (code "46") (name "unconnected-(IMU_MAX232-R1OUT-Pad12)") (class "Default")
      (node (ref "IMU_MAX232") (pin "12") (pinfunction "R1OUT_12") (pintype "output+no_connect"))
    )
    (net (code "47") (name "unconnected-(IMU_MAX232-R2IN-Pad8)") (class "Default")
      (node (ref "IMU_MAX232") (pin "8") (pinfunction "R2IN_8") (pintype "input+no_connect"))
    )
    (net (code "48") (name "unconnected-(IMU_MAX232-R2OUT-Pad9)") (class "Default")
      (node (ref "IMU_MAX232") (pin "9") (pinfunction "R2OUT_9") (pintype "output+no_connect"))
    )
    (net (code "49") (name "unconnected-(IMU_MAX232-T2IN-Pad10)") (class "Default")
      (node (ref "IMU_MAX232") (pin "10") (pinfunction "T2IN_10") (pintype "input+no_connect"))
    )
    (net (code "50") (name "unconnected-(IMU_MAX232-T2OUT-Pad7)") (class "Default")
      (node (ref "IMU_MAX232") (pin "7") (pinfunction "T2OUT_7") (pintype "output+no_connect"))
    )
    (net (code "51") (name "unconnected-(IMU_MPU6050-AD0-Pad6)") (class "Default")
      (node (ref "IMU_MPU6050") (pin "6") (pinfunction "AD0_6") (pintype "passive+no_connect"))
    )
    (net (code "52") (name "unconnected-(IMU_MPU6050-INT-Pad7)") (class "Default")
      (node (ref "IMU_MPU6050") (pin "7") (pinfunction "INT_7") (pintype "passive+no_connect"))
    )
    (net (code "53") (name "unconnected-(IMU_MPU6050-XCL-Pad5)") (class "Default")
      (node (ref "IMU_MPU6050") (pin "5") (pinfunction "XCL_5") (pintype "passive+no_connect"))
    )
    (net (code "54") (name "unconnected-(IMU_MPU6050-XDA-Pad4)") (class "Default")
      (node (ref "IMU_MPU6050") (pin "4") (pinfunction "XDA_4") (pintype "passive+no_connect"))
    )
    (net (code "55") (name "unconnected-(IMU_OUT-Pad1)") (class "Default")
      (node (ref "IMU_OUT") (pin "1") (pinfunction "1_1") (pintype "passive+no_connect"))
    )
    (net (code "56") (name "unconnected-(Nano-+5V-Pad27)") (class "Default")
      (node (ref "Nano") (pin "27") (pinfunction "+5V_27") (pintype "passive"))
    )
    (net (code "57") (name "unconnected-(Nano-3V3-Pad17)") (class "Default")
      (node (ref "Nano") (pin "17") (pinfunction "3V3_17") (pintype "passive"))
    )
    (net (code "58") (name "unconnected-(Nano-A0-Pad19)") (class "Default")
      (node (ref "Nano") (pin "19") (pinfunction "A0_19") (pintype "passive"))
    )
    (net (code "59") (name "unconnected-(Nano-A1-Pad20)") (class "Default")
      (node (ref "Nano") (pin "20") (pinfunction "A1_20") (pintype "passive"))
    )
    (net (code "60") (name "unconnected-(Nano-A2-Pad21)") (class "Default")
      (node (ref "Nano") (pin "21") (pinfunction "A2_21") (pintype "passive"))
    )
    (net (code "61") (name "unconnected-(Nano-A3-Pad22)") (class "Default")
      (node (ref "Nano") (pin "22") (pinfunction "A3_22") (pintype "passive"))
    )
    (net (code "62") (name "unconnected-(Nano-A6-Pad25)") (class "Default")
      (node (ref "Nano") (pin "25") (pinfunction "A6_25") (pintype "passive"))
    )
    (net (code "63") (name "unconnected-(Nano-A7-Pad26)") (class "Default")
      (node (ref "Nano") (pin "26") (pinfunction "A7_26") (pintype "passive"))
    )
    (net (code "64") (name "unconnected-(Nano-AREF-Pad18)") (class "Default")
      (node (ref "Nano") (pin "18") (pinfunction "AREF_18") (pintype "passive"))
    )
    (net (code "65") (name "unconnected-(Nano-D7-Pad10)") (class "Default")
      (node (ref "Nano") (pin "10") (pinfunction "D7_10") (pintype "passive"))
    )
    (net (code "66") (name "unconnected-(Nano-D8-Pad11)") (class "Default")
      (node (ref "Nano") (pin "11") (pinfunction "D8_11") (pintype "passive"))
    )
    (net (code "67") (name "unconnected-(Nano-D9-Pad12)") (class "Default")
      (node (ref "Nano") (pin "12") (pinfunction "D9_12") (pintype "passive"))
    )
    (net (code "68") (name "unconnected-(Nano-D10-Pad13)") (class "Default")
      (node (ref "Nano") (pin "13") (pinfunction "D10_13") (pintype "passive"))
    )
    (net (code "69") (name "unconnected-(Nano-D11-Pad14)") (class "Default")
      (node (ref "Nano") (pin "14") (pinfunction "D11_14") (pintype "passive"))
    )
    (net (code "70") (name "unconnected-(Nano-D12-Pad15)") (class "Default")
      (node (ref "Nano") (pin "15") (pinfunction "D12_15") (pintype "passive"))
    )
    (net (code "71") (name "unconnected-(Nano-D13-Pad16)") (class "Default")
      (node (ref "Nano") (pin "16") (pinfunction "D13_16") (pintype "passive"))
    )
    (net (code "72") (name "unconnected-(Nano-RST-Pad3)") (class "Default")
      (node (ref "Nano") (pin "3") (pinfunction "RST_3") (pintype "passive"))
    )
    (net (code "73") (name "unconnected-(Nano-RST-Pad28)") (class "Default")
      (node (ref "Nano") (pin "28") (pinfunction "RST_28") (pintype "passive"))
    )
    (net (code "74") (name "unconnected-(Nano-RX-Pad2)") (class "Default")
      (node (ref "Nano") (pin "2") (pinfunction "RX_2") (pintype "passive"))
    )
    (net (code "75") (name "unconnected-(Nano-TX-Pad1)") (class "Default")
      (node (ref "Nano") (pin "1") (pinfunction "TX_1") (pintype "passive"))
    )
  )
)
